# led-er-2xRJ46.net
KiCad netlist of a schematic drawn in EAGLE
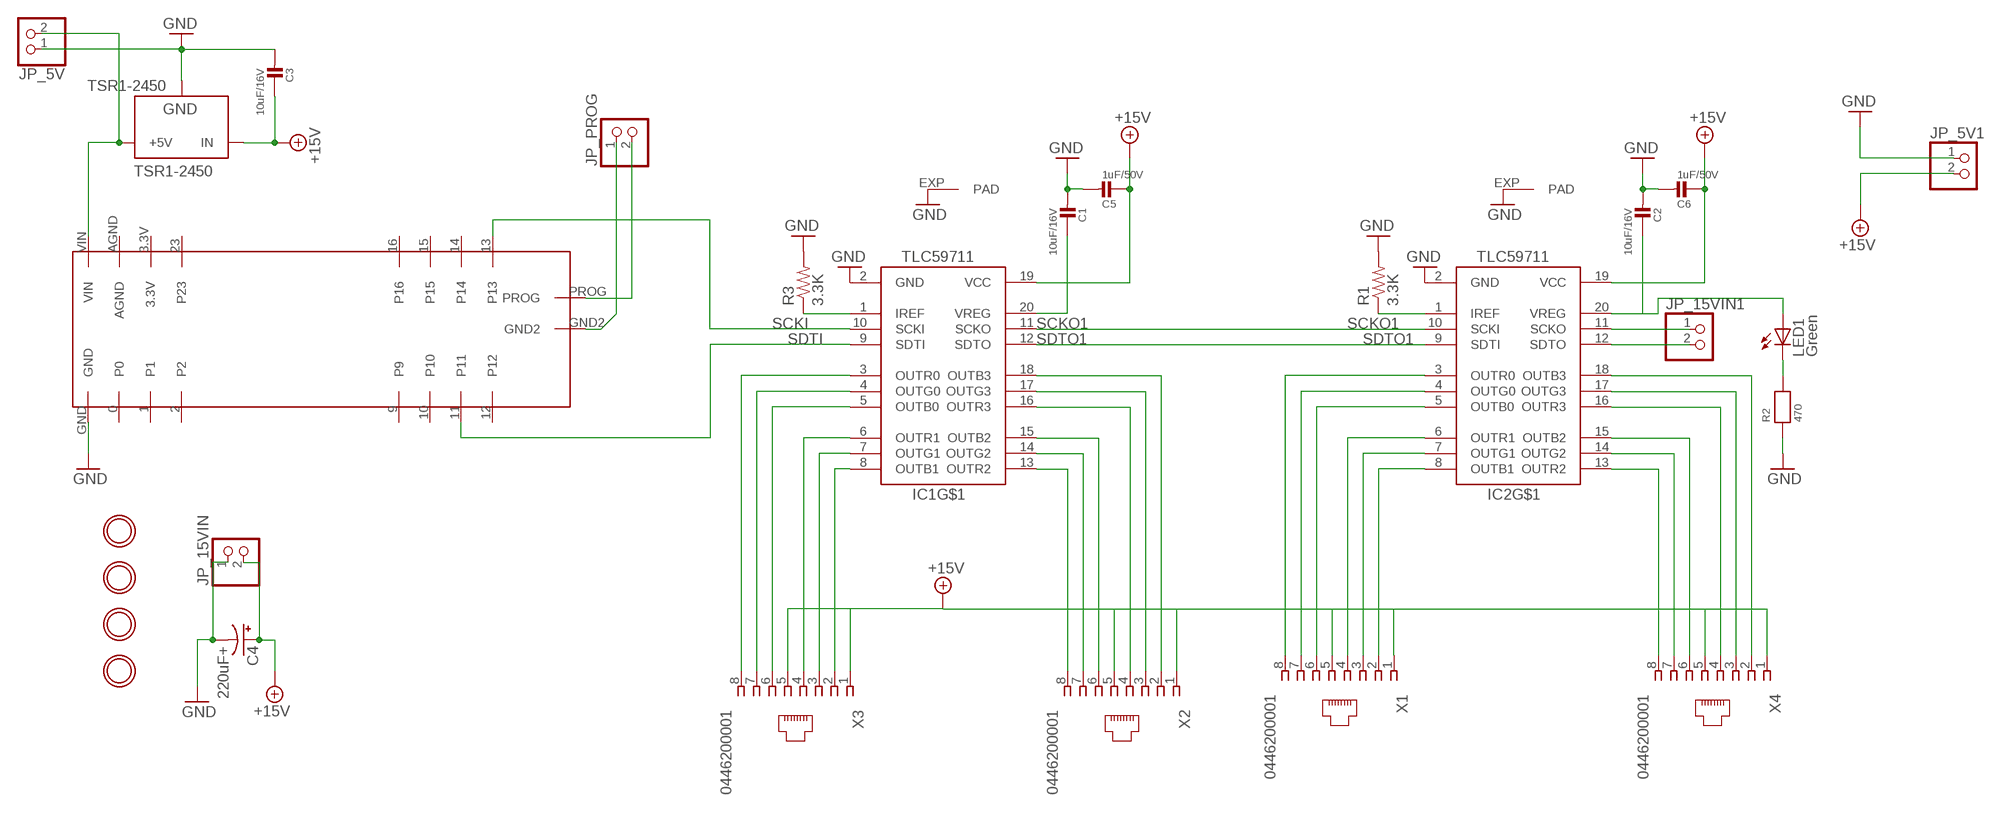
[diagram p0: schematic, sheet 1]

(export (version "E")
  (design (tool "Eeschema 10.0.6"))
  (components
    (comp (ref "C1")
      (value "10uF/16V")
      (footprint "eagle-import:0805")
      (libsource (lib "eagle-import") (part "CAP_CERAMIC0805"))
    )
    (comp (ref "C2")
      (value "10uF/16V")
      (footprint "eagle-import:0805")
      (libsource (lib "eagle-import") (part "CAP_CERAMIC0805"))
    )
    (comp (ref "C3")
      (value "10uF/16V")
      (footprint "eagle-import:0805")
      (libsource (lib "eagle-import") (part "CAP_CERAMIC0805"))
    )
    (comp (ref "C4")
      (value "220uF+")
      (footprint "eagle-import:E5-8,5")
      (libsource (lib "eagle-import") (part "CPOL-USE5-8.5"))
    )
    (comp (ref "C5")
      (value "1uF/50V")
      (footprint "eagle-import:0805")
      (libsource (lib "eagle-import") (part "CAP_CERAMIC0805"))
    )
    (comp (ref "C6")
      (value "1uF/50V")
      (footprint "eagle-import:0805")
      (libsource (lib "eagle-import") (part "CAP_CERAMIC0805"))
    )
    (comp (ref "IC1")
      (value "TLC59711")
      (footprint "eagle-import:HTSSOP20DAP")
      (libsource (lib "eagle-import") (part "TLC59711"))
    )
    (comp (ref "IC2")
      (value "TLC59711")
      (footprint "eagle-import:HTSSOP20DAP")
      (libsource (lib "eagle-import") (part "TLC59711"))
    )
    (comp (ref "JP_5V")
      (value "HEADER-1X2")
      (footprint "eagle-import:1X02_OVAL")
      (libsource (lib "eagle-import") (part "HEADER-1X2"))
    )
    (comp (ref "JP_5V1")
      (value "HEADER-1X2")
      (footprint "eagle-import:1X02_OVAL")
      (libsource (lib "eagle-import") (part "HEADER-1X2"))
    )
    (comp (ref "JP_15VIN")
      (value "HEADER-1X2")
      (footprint "eagle-import:1X02_OVAL")
      (libsource (lib "eagle-import") (part "HEADER-1X2"))
    )
    (comp (ref "JP_15VIN1")
      (value "HEADER-1X2")
      (footprint "eagle-import:1X02_OVAL")
      (libsource (lib "eagle-import") (part "HEADER-1X2"))
    )
    (comp (ref "JP_PROG")
      (value "HEADER-1X2")
      (footprint "eagle-import:1X02_OVAL")
      (libsource (lib "eagle-import") (part "HEADER-1X2"))
    )
    (comp (ref "LED1")
      (value "Green")
      (footprint "eagle-import:CHIP-LED0805")
      (libsource (lib "eagle-import") (part "LEDCHIP-LED0805"))
    )
    (comp (ref "R1")
      (value "3.3K")
      (footprint "eagle-import:0805-THM-7")
      (libsource (lib "eagle-import") (part "R-US_FLIPFLOP7"))
    )
    (comp (ref "R2")
      (value "470")
      (footprint "eagle-import:0805")
      (libsource (lib "eagle-import") (part "RESISTOR0805"))
    )
    (comp (ref "R3")
      (value "3.3K")
      (footprint "eagle-import:0805-THM-7")
      (libsource (lib "eagle-import") (part "R-US_FLIPFLOP7"))
    )
    (comp (ref "TSR1-2450")
      (value "TSR1-2450")
      (footprint "eagle-import:TSR-1")
      (libsource (lib "eagle-import") (part "TSR1-2450"))
    )
    (comp (ref "U$1")
      (value "MOUNTINGHOLE")
      (footprint "eagle-import:MOUNTINGHOLE_3.0_PLATED")
      (libsource (lib "eagle-import") (part "MOUNTINGHOLE"))
    )
    (comp (ref "U$2")
      (value "MOUNTINGHOLE")
      (footprint "eagle-import:MOUNTINGHOLE_3.0_PLATED")
      (libsource (lib "eagle-import") (part "MOUNTINGHOLE"))
    )
    (comp (ref "U$3")
      (value "MOUNTINGHOLE")
      (footprint "eagle-import:MOUNTINGHOLE_3.0_PLATED")
      (libsource (lib "eagle-import") (part "MOUNTINGHOLE"))
    )
    (comp (ref "U$4")
      (value "MOUNTINGHOLE")
      (footprint "eagle-import:MOUNTINGHOLE_3.0_PLATED")
      (libsource (lib "eagle-import") (part "MOUNTINGHOLE"))
    )
    (comp (ref "U$5")
      (value "TEENSY_LEDER")
      (footprint "eagle-import:TEENSY_LEDER")
      (libsource (lib "eagle-import") (part "TEENSY_LEDER"))
    )
    (comp (ref "X1")
      (value "0446200001")
      (footprint "eagle-import:0446200001")
      (libsource (lib "eagle-import") (part "0446200001"))
    )
    (comp (ref "X2")
      (value "0446200001")
      (footprint "eagle-import:0446200001")
      (libsource (lib "eagle-import") (part "0446200001"))
    )
    (comp (ref "X3")
      (value "0446200001")
      (footprint "eagle-import:0446200001")
      (libsource (lib "eagle-import") (part "0446200001"))
    )
    (comp (ref "X4")
      (value "0446200001")
      (footprint "eagle-import:0446200001")
      (libsource (lib "eagle-import") (part "0446200001"))
    )
  )
  (nets
    (net (code "1") (name "+15V") (class "Default")
      (node (ref "C3") (pin "1") (pinfunction "P$1_1") (pintype "passive"))
      (node (ref "C4") (pin "+") (pinfunction "+_+") (pintype "passive"))
      (node (ref "C5") (pin "1") (pinfunction "P$1_1") (pintype "passive"))
      (node (ref "C6") (pin "1") (pinfunction "P$1_1") (pintype "passive"))
      (node (ref "IC1") (pin "19") (pinfunction "VCC_19") (pintype "power_in"))
      (node (ref "IC2") (pin "19") (pinfunction "VCC_19") (pintype "power_in"))
      (node (ref "JP_15VIN") (pin "2") (pinfunction "2_2") (pintype "passive"))
      (node (ref "JP_5V1") (pin "2") (pinfunction "2_2") (pintype "passive"))
      (node (ref "TSR1-2450") (pin "1") (pinfunction "IN_1") (pintype "power_in"))
      (node (ref "X1") (pin "1") (pinfunction "1_1") (pintype "passive"))
      (node (ref "X1") (pin "5") (pinfunction "5_5") (pintype "passive"))
      (node (ref "X2") (pin "1") (pinfunction "1_1") (pintype "passive"))
      (node (ref "X2") (pin "5") (pinfunction "5_5") (pintype "passive"))
      (node (ref "X3") (pin "1") (pinfunction "1_1") (pintype "passive"))
      (node (ref "X3") (pin "5") (pinfunction "5_5") (pintype "passive"))
      (node (ref "X4") (pin "1") (pinfunction "1_1") (pintype "passive"))
      (node (ref "X4") (pin "5") (pinfunction "5_5") (pintype "passive"))
    )
    (net (code "2") (name "/SCKI") (class "Default")
      (node (ref "IC1") (pin "10") (pinfunction "SCKI_10") (pintype "input"))
      (node (ref "U$5") (pin "13") (pinfunction "P13_13") (pintype "bidirectional"))
    )
    (net (code "3") (name "/SCKO1") (class "Default")
      (node (ref "IC1") (pin "11") (pinfunction "SCKO_11") (pintype "output"))
      (node (ref "IC2") (pin "10") (pinfunction "SCKI_10") (pintype "input"))
    )
    (net (code "4") (name "/SDTI") (class "Default")
      (node (ref "IC1") (pin "9") (pinfunction "SDTI_9") (pintype "input"))
      (node (ref "U$5") (pin "11") (pinfunction "P11_11") (pintype "bidirectional"))
    )
    (net (code "5") (name "/SDTO1") (class "Default")
      (node (ref "IC1") (pin "12") (pinfunction "SDTO_12") (pintype "output"))
      (node (ref "IC2") (pin "9") (pinfunction "SDTI_9") (pintype "input"))
    )
    (net (code "6") (name "GND") (class "Default")
      (node (ref "C1") (pin "2") (pinfunction "P$2_2") (pintype "passive"))
      (node (ref "C2") (pin "2") (pinfunction "P$2_2") (pintype "passive"))
      (node (ref "C3") (pin "2") (pinfunction "P$2_2") (pintype "passive"))
      (node (ref "C4") (pin "-") (pinfunction "-_-") (pintype "passive"))
      (node (ref "C5") (pin "2") (pinfunction "P$2_2") (pintype "passive"))
      (node (ref "C6") (pin "2") (pinfunction "P$2_2") (pintype "passive"))
      (node (ref "IC1") (pin "2") (pinfunction "GND_2") (pintype "power_in"))
      (node (ref "IC1") (pin "EXP") (pinfunction "PAD_EXP") (pintype "passive"))
      (node (ref "IC2") (pin "2") (pinfunction "GND_2") (pintype "power_in"))
      (node (ref "IC2") (pin "EXP") (pinfunction "PAD_EXP") (pintype "passive"))
      (node (ref "JP_15VIN") (pin "1") (pinfunction "1_1") (pintype "passive"))
      (node (ref "JP_5V") (pin "1") (pinfunction "1_1") (pintype "passive"))
      (node (ref "JP_5V1") (pin "1") (pinfunction "1_1") (pintype "passive"))
      (node (ref "R1") (pin "2") (pinfunction "2_2") (pintype "passive"))
      (node (ref "R2") (pin "1") (pinfunction "1_1") (pintype "passive"))
      (node (ref "R3") (pin "2") (pinfunction "2_2") (pintype "passive"))
      (node (ref "TSR1-2450") (pin "2") (pinfunction "GND_2") (pintype "power_in"))
      (node (ref "U$5") (pin "GND") (pinfunction "GND_GND") (pintype "bidirectional"))
    )
    (net (code "7") (name "Net-(C1-P$1)") (class "Default")
      (node (ref "C1") (pin "1") (pinfunction "P$1_1") (pintype "passive"))
      (node (ref "IC1") (pin "20") (pinfunction "VREG_20") (pintype "bidirectional"))
    )
    (net (code "8") (name "Net-(C2-P$1)") (class "Default")
      (node (ref "C2") (pin "1") (pinfunction "P$1_1") (pintype "passive"))
      (node (ref "IC2") (pin "20") (pinfunction "VREG_20") (pintype "bidirectional"))
      (node (ref "LED1") (pin "A") (pinfunction "A_A") (pintype "passive"))
    )
    (net (code "9") (name "Net-(IC1A-IREF)") (class "Default")
      (node (ref "IC1") (pin "1") (pinfunction "IREF_1") (pintype "bidirectional"))
      (node (ref "R3") (pin "1") (pinfunction "1_1") (pintype "passive"))
    )
    (net (code "10") (name "Net-(IC1A-OUTB0)") (class "Default")
      (node (ref "IC1") (pin "5") (pinfunction "OUTB0_5") (pintype "open_collector"))
      (node (ref "X3") (pin "6") (pinfunction "6_6") (pintype "passive"))
    )
    (net (code "11") (name "Net-(IC1A-OUTB1)") (class "Default")
      (node (ref "IC1") (pin "8") (pinfunction "OUTB1_8") (pintype "open_collector"))
      (node (ref "X3") (pin "2") (pinfunction "2_2") (pintype "passive"))
    )
    (net (code "12") (name "Net-(IC1A-OUTB2)") (class "Default")
      (node (ref "IC1") (pin "15") (pinfunction "OUTB2_15") (pintype "open_collector"))
      (node (ref "X2") (pin "6") (pinfunction "6_6") (pintype "passive"))
    )
    (net (code "13") (name "Net-(IC1A-OUTB3)") (class "Default")
      (node (ref "IC1") (pin "18") (pinfunction "OUTB3_18") (pintype "open_collector"))
      (node (ref "X2") (pin "2") (pinfunction "2_2") (pintype "passive"))
    )
    (net (code "14") (name "Net-(IC1A-OUTG0)") (class "Default")
      (node (ref "IC1") (pin "4") (pinfunction "OUTG0_4") (pintype "open_collector"))
      (node (ref "X3") (pin "7") (pinfunction "7_7") (pintype "passive"))
    )
    (net (code "15") (name "Net-(IC1A-OUTG1)") (class "Default")
      (node (ref "IC1") (pin "7") (pinfunction "OUTG1_7") (pintype "open_collector"))
      (node (ref "X3") (pin "3") (pinfunction "3_3") (pintype "passive"))
    )
    (net (code "16") (name "Net-(IC1A-OUTG2)") (class "Default")
      (node (ref "IC1") (pin "14") (pinfunction "OUTG2_14") (pintype "open_collector"))
      (node (ref "X2") (pin "7") (pinfunction "7_7") (pintype "passive"))
    )
    (net (code "17") (name "Net-(IC1A-OUTG3)") (class "Default")
      (node (ref "IC1") (pin "17") (pinfunction "OUTG3_17") (pintype "open_collector"))
      (node (ref "X2") (pin "3") (pinfunction "3_3") (pintype "passive"))
    )
    (net (code "18") (name "Net-(IC1A-OUTR0)") (class "Default")
      (node (ref "IC1") (pin "3") (pinfunction "OUTR0_3") (pintype "open_collector"))
      (node (ref "X3") (pin "8") (pinfunction "8_8") (pintype "passive"))
    )
    (net (code "19") (name "Net-(IC1A-OUTR1)") (class "Default")
      (node (ref "IC1") (pin "6") (pinfunction "OUTR1_6") (pintype "open_collector"))
      (node (ref "X3") (pin "4") (pinfunction "4_4") (pintype "passive"))
    )
    (net (code "20") (name "Net-(IC1A-OUTR2)") (class "Default")
      (node (ref "IC1") (pin "13") (pinfunction "OUTR2_13") (pintype "open_collector"))
      (node (ref "X2") (pin "8") (pinfunction "8_8") (pintype "passive"))
    )
    (net (code "21") (name "Net-(IC1A-OUTR3)") (class "Default")
      (node (ref "IC1") (pin "16") (pinfunction "OUTR3_16") (pintype "open_collector"))
      (node (ref "X2") (pin "4") (pinfunction "4_4") (pintype "passive"))
    )
    (net (code "22") (name "Net-(IC2A-IREF)") (class "Default")
      (node (ref "IC2") (pin "1") (pinfunction "IREF_1") (pintype "bidirectional"))
      (node (ref "R1") (pin "1") (pinfunction "1_1") (pintype "passive"))
    )
    (net (code "23") (name "Net-(IC2A-OUTB0)") (class "Default")
      (node (ref "IC2") (pin "5") (pinfunction "OUTB0_5") (pintype "open_collector"))
      (node (ref "X1") (pin "6") (pinfunction "6_6") (pintype "passive"))
    )
    (net (code "24") (name "Net-(IC2A-OUTB1)") (class "Default")
      (node (ref "IC2") (pin "8") (pinfunction "OUTB1_8") (pintype "open_collector"))
      (node (ref "X1") (pin "2") (pinfunction "2_2") (pintype "passive"))
    )
    (net (code "25") (name "Net-(IC2A-OUTB2)") (class "Default")
      (node (ref "IC2") (pin "15") (pinfunction "OUTB2_15") (pintype "open_collector"))
      (node (ref "X4") (pin "6") (pinfunction "6_6") (pintype "passive"))
    )
    (net (code "26") (name "Net-(IC2A-OUTB3)") (class "Default")
      (node (ref "IC2") (pin "18") (pinfunction "OUTB3_18") (pintype "open_collector"))
      (node (ref "X4") (pin "2") (pinfunction "2_2") (pintype "passive"))
    )
    (net (code "27") (name "Net-(IC2A-OUTG0)") (class "Default")
      (node (ref "IC2") (pin "4") (pinfunction "OUTG0_4") (pintype "open_collector"))
      (node (ref "X1") (pin "7") (pinfunction "7_7") (pintype "passive"))
    )
    (net (code "28") (name "Net-(IC2A-OUTG1)") (class "Default")
      (node (ref "IC2") (pin "7") (pinfunction "OUTG1_7") (pintype "open_collector"))
      (node (ref "X1") (pin "3") (pinfunction "3_3") (pintype "passive"))
    )
    (net (code "29") (name "Net-(IC2A-OUTG2)") (class "Default")
      (node (ref "IC2") (pin "14") (pinfunction "OUTG2_14") (pintype "open_collector"))
      (node (ref "X4") (pin "7") (pinfunction "7_7") (pintype "passive"))
    )
    (net (code "30") (name "Net-(IC2A-OUTG3)") (class "Default")
      (node (ref "IC2") (pin "17") (pinfunction "OUTG3_17") (pintype "open_collector"))
      (node (ref "X4") (pin "3") (pinfunction "3_3") (pintype "passive"))
    )
    (net (code "31") (name "Net-(IC2A-OUTR0)") (class "Default")
      (node (ref "IC2") (pin "3") (pinfunction "OUTR0_3") (pintype "open_collector"))
      (node (ref "X1") (pin "8") (pinfunction "8_8") (pintype "passive"))
    )
    (net (code "32") (name "Net-(IC2A-OUTR1)") (class "Default")
      (node (ref "IC2") (pin "6") (pinfunction "OUTR1_6") (pintype "open_collector"))
      (node (ref "X1") (pin "4") (pinfunction "4_4") (pintype "passive"))
    )
    (net (code "33") (name "Net-(IC2A-OUTR2)") (class "Default")
      (node (ref "IC2") (pin "13") (pinfunction "OUTR2_13") (pintype "open_collector"))
      (node (ref "X4") (pin "8") (pinfunction "8_8") (pintype "passive"))
    )
    (net (code "34") (name "Net-(IC2A-OUTR3)") (class "Default")
      (node (ref "IC2") (pin "16") (pinfunction "OUTR3_16") (pintype "open_collector"))
      (node (ref "X4") (pin "4") (pinfunction "4_4") (pintype "passive"))
    )
    (net (code "35") (name "Net-(IC2A-SCKO)") (class "Default")
      (node (ref "IC2") (pin "11") (pinfunction "SCKO_11") (pintype "output"))
      (node (ref "JP_15VIN1") (pin "1") (pinfunction "1_1") (pintype "passive"))
    )
    (net (code "36") (name "Net-(IC2A-SDTO)") (class "Default")
      (node (ref "IC2") (pin "12") (pinfunction "SDTO_12") (pintype "output"))
      (node (ref "JP_15VIN1") (pin "2") (pinfunction "2_2") (pintype "passive"))
    )
    (net (code "37") (name "Net-(JP_PROG-Pad1)") (class "Default")
      (node (ref "JP_PROG") (pin "1") (pinfunction "1_1") (pintype "passive"))
      (node (ref "U$5") (pin "GND2") (pinfunction "GND2_GND2") (pintype "bidirectional"))
    )
    (net (code "38") (name "Net-(JP_PROG-Pad2)") (class "Default")
      (node (ref "JP_PROG") (pin "2") (pinfunction "2_2") (pintype "passive"))
      (node (ref "U$5") (pin "PROG") (pinfunction "PROG_PROG") (pintype "bidirectional"))
    )
    (net (code "39") (name "Net-(LED1-PadC)") (class "Default")
      (node (ref "LED1") (pin "C") (pinfunction "C_C") (pintype "passive"))
      (node (ref "R2") (pin "2") (pinfunction "2_2") (pintype "passive"))
    )
    (net (code "40") (name "Net-(TSR1-2450-+5V)") (class "Default")
      (node (ref "JP_5V") (pin "2") (pinfunction "2_2") (pintype "passive"))
      (node (ref "TSR1-2450") (pin "3") (pinfunction "+5V_3") (pintype "power_in"))
      (node (ref "U$5") (pin "VIN") (pinfunction "VIN_VIN") (pintype "bidirectional"))
    )
    (net (code "41") (name "unconnected-(U$5-P0-Pad0)") (class "Default")
      (node (ref "U$5") (pin "0") (pinfunction "P0_0") (pintype "bidirectional"))
    )
    (net (code "42") (name "unconnected-(U$5-P1-Pad1)") (class "Default")
      (node (ref "U$5") (pin "1") (pinfunction "P1_1") (pintype "bidirectional"))
    )
    (net (code "43") (name "unconnected-(U$5-P2-Pad2)") (class "Default")
      (node (ref "U$5") (pin "2") (pinfunction "P2_2") (pintype "bidirectional"))
    )
    (net (code "44") (name "unconnected-(U$5-P9-Pad9)") (class "Default")
      (node (ref "U$5") (pin "9") (pinfunction "P9_9") (pintype "bidirectional"))
    )
    (net (code "45") (name "unconnected-(U$5-P10-Pad10)") (class "Default")
      (node (ref "U$5") (pin "10") (pinfunction "P10_10") (pintype "bidirectional"))
    )
    (net (code "46") (name "unconnected-(U$5-P12-Pad12)") (class "Default")
      (node (ref "U$5") (pin "12") (pinfunction "P12_12") (pintype "bidirectional"))
    )
    (net (code "47") (name "unconnected-(U$5-P14-Pad14)") (class "Default")
      (node (ref "U$5") (pin "14") (pinfunction "P14_14") (pintype "bidirectional"))
    )
    (net (code "48") (name "unconnected-(U$5-P15-Pad15)") (class "Default")
      (node (ref "U$5") (pin "15") (pinfunction "P15_15") (pintype "bidirectional"))
    )
    (net (code "49") (name "unconnected-(U$5-P16-Pad16)") (class "Default")
      (node (ref "U$5") (pin "16") (pinfunction "P16_16") (pintype "bidirectional"))
    )
    (net (code "50") (name "unconnected-(U$5-P23-Pad23)") (class "Default")
      (node (ref "U$5") (pin "23") (pinfunction "P23_23") (pintype "bidirectional"))
    )
    (net (code "51") (name "unconnected-(U$5-Pad3.3V)") (class "Default")
      (node (ref "U$5") (pin "3.3V") (pinfunction "3.3V_3.3V") (pintype "bidirectional"))
    )
    (net (code "52") (name "unconnected-(U$5-PadAGND)") (class "Default")
      (node (ref "U$5") (pin "AGND") (pinfunction "AGND_AGND") (pintype "bidirectional"))
    )
  )
)
